# thing-plus-carrier.net
KiCad netlist of a schematic drawn in EAGLE
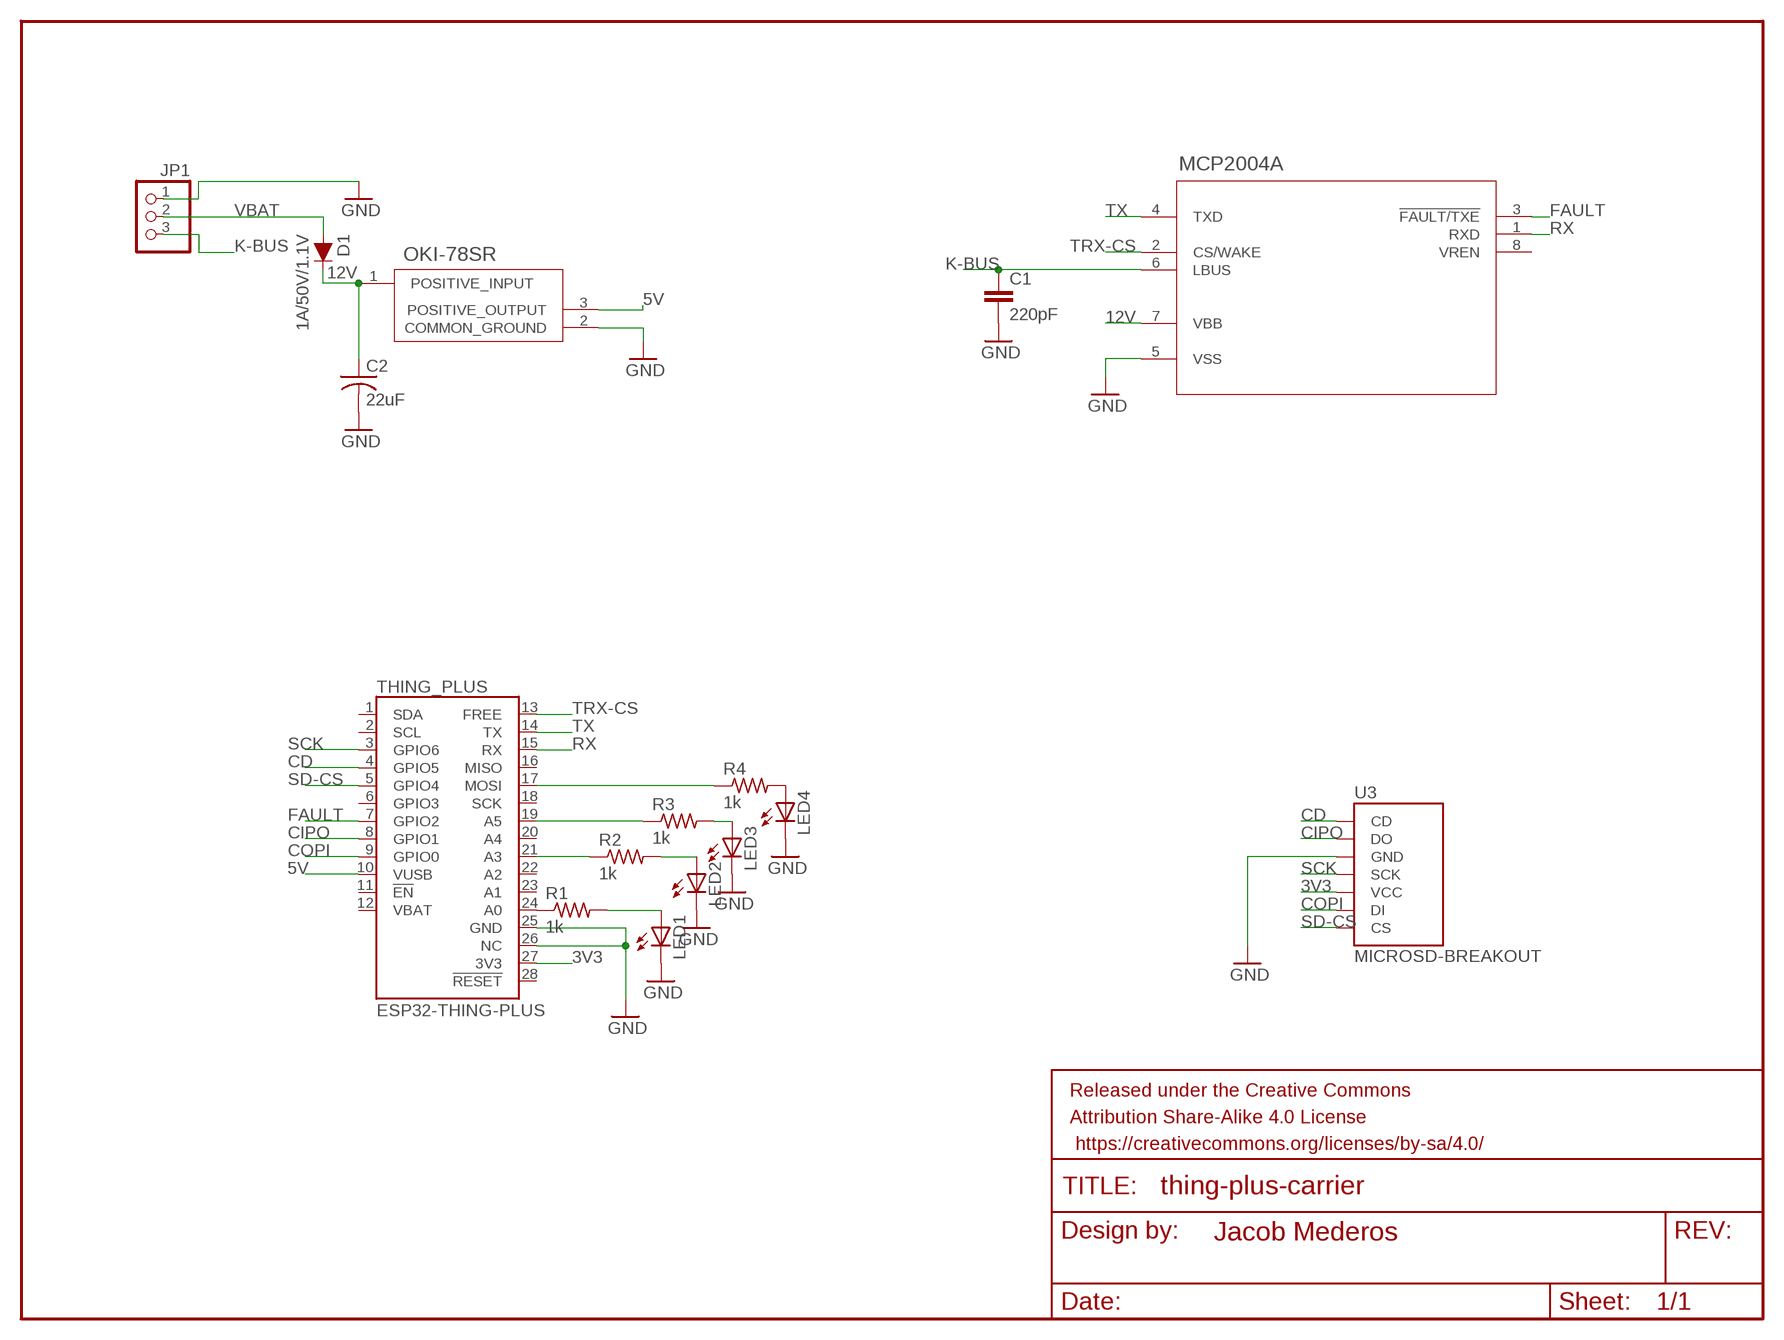
[diagram p0: schematic, sheet 1]

(export (version "E")
  (design (tool "Eeschema 10.0.6"))
  (components
    (comp (ref "C1")
      (value "220pF")
      (footprint "eagle-import:CAP-PTH-SMALL-KIT")
      (libsource (lib "eagle-import") (part "0.1UF-KIT-EZ-50V-20%"))
    )
    (comp (ref "C2")
      (value "22uF")
      (footprint "eagle-import:C1206K")
      (libsource (lib "eagle-import") (part "C-USC1206K"))
    )
    (comp (ref "D1")
      (value "1A/50V/1.1V")
      (footprint "eagle-import:DIODE-1N4001")
      (libsource (lib "eagle-import") (part "DIODE-PTH"))
    )
    (comp (ref "ESP32-THING-PLUS")
      (value "THING_PLUS")
      (footprint "eagle-import:THING_PLUS")
      (libsource (lib "eagle-import") (part "THING_PLUS"))
    )
    (comp (ref "FRAME1")
      (value "FRAME-LETTERNO_PACKAGE")
      (footprint "eagle-import:DUMMY")
      (fields (field (name "DESIGNER") "Jacob Mederos") (field (name "DESIGNER_1") "Jacob Mederos"))
      (libsource (lib "eagle-import") (part "FRAME-LETTERNO_PACKAGE"))
    )
    (comp (ref "JP1")
      (value "PINHD-1X3")
      (footprint "eagle-import:1X03")
      (libsource (lib "eagle-import") (part "PINHD-1X3"))
    )
    (comp (ref "LED1")
      (value "LEDCHIPLED_0805")
      (footprint "eagle-import:CHIPLED_0805")
      (libsource (lib "eagle-import") (part "LEDCHIPLED_0805"))
    )
    (comp (ref "LED2")
      (value "LEDCHIPLED_0805")
      (footprint "eagle-import:CHIPLED_0805")
      (libsource (lib "eagle-import") (part "LEDCHIPLED_0805"))
    )
    (comp (ref "LED3")
      (value "LEDCHIPLED_0805")
      (footprint "eagle-import:CHIPLED_0805")
      (libsource (lib "eagle-import") (part "LEDCHIPLED_0805"))
    )
    (comp (ref "LED4")
      (value "LEDCHIPLED_0805")
      (footprint "eagle-import:CHIPLED_0805")
      (libsource (lib "eagle-import") (part "LEDCHIPLED_0805"))
    )
    (comp (ref "MCP2004A")
      (value "MCP2004A-E/SNSOIC8_4P9X3P9MC_MCH-M")
      (footprint "eagle-import:SOIC8_4P9X3P9MC_MCH-M")
      (fields
        (field (name "MANUFACTURER_PART_NUMBER") "MCP2004A-E/SN")
        (field (name "COPYRIGHT") "Copyright (C) 2018 Accelerated Designs. All rights reserved")
      )
      (libsource (lib "eagle-import") (part "MCP2004A-E/SNSOIC8_4P9X3P9MC_MCH-M"))
    )
    (comp (ref "OKI-78SR")
      (value "OKI-78SR-5/1.5-W36H-C")
      (footprint "eagle-import:OKI-78SR-5_1.5-W36H-C_MUR")
      (fields (field (name "COPYRIGHT") "Copyright (C) 2018 Accelerated Designs. All rights reserved"))
      (libsource (lib "eagle-import") (part "OKI-78SR-5/1.5-W36H-C"))
    )
    (comp (ref "R1")
      (value "1k")
      (footprint "eagle-import:R0805")
      (libsource (lib "eagle-import") (part "R-US_R0805"))
    )
    (comp (ref "R2")
      (value "1k")
      (footprint "eagle-import:R0805")
      (libsource (lib "eagle-import") (part "R-US_R0805"))
    )
    (comp (ref "R3")
      (value "1k")
      (footprint "eagle-import:R0805")
      (libsource (lib "eagle-import") (part "R-US_R0805"))
    )
    (comp (ref "R4")
      (value "1k")
      (footprint "eagle-import:R0805")
      (libsource (lib "eagle-import") (part "R-US_R0805"))
    )
    (comp (ref "U3")
      (value "MICROSD-BREAKOUT")
      (footprint "eagle-import:MICROSD-BREAKOUT")
      (libsource (lib "eagle-import") (part "MICROSD-BREAKOUT"))
    )
  )
  (nets
    (net (code "1") (name "/3V3") (class "Default")
      (node (ref "ESP32-THING-PLUS") (pin "27") (pinfunction "3V3_27") (pintype "bidirectional"))
      (node (ref "U3") (pin "VCC") (pinfunction "VCC_VCC") (pintype "bidirectional"))
    )
    (net (code "2") (name "/5V") (class "Default")
      (node (ref "ESP32-THING-PLUS") (pin "10") (pinfunction "VUSB_10") (pintype "bidirectional"))
      (node (ref "OKI-78SR") (pin "3") (pinfunction "POSITIVE_OUTPUT_3") (pintype "passive"))
    )
    (net (code "3") (name "/12V") (class "Default")
      (node (ref "C2") (pin "1") (pinfunction "1_1") (pintype "passive"))
      (node (ref "D1") (pin "C") (pinfunction "C_C") (pintype "passive"))
      (node (ref "MCP2004A") (pin "7") (pinfunction "VBB_7") (pintype "power_in"))
      (node (ref "OKI-78SR") (pin "1") (pinfunction "POSITIVE_INPUT_1") (pintype "input"))
    )
    (net (code "4") (name "/CD") (class "Default")
      (node (ref "ESP32-THING-PLUS") (pin "4") (pinfunction "GPIO5_4") (pintype "bidirectional"))
      (node (ref "U3") (pin "CD") (pinfunction "CD_CD") (pintype "bidirectional"))
    )
    (net (code "5") (name "/CIPO") (class "Default")
      (node (ref "ESP32-THING-PLUS") (pin "8") (pinfunction "GPIO1_8") (pintype "bidirectional"))
      (node (ref "U3") (pin "DO") (pinfunction "DO_DO") (pintype "bidirectional"))
    )
    (net (code "6") (name "/COPI") (class "Default")
      (node (ref "ESP32-THING-PLUS") (pin "9") (pinfunction "GPIO0_9") (pintype "bidirectional"))
      (node (ref "U3") (pin "DI") (pinfunction "DI_DI") (pintype "bidirectional"))
    )
    (net (code "7") (name "/FAULT") (class "Default")
      (node (ref "ESP32-THING-PLUS") (pin "7") (pinfunction "GPIO2_7") (pintype "bidirectional"))
      (node (ref "MCP2004A") (pin "3") (pinfunction "~{FAULT/TXE}_3") (pintype "output"))
    )
    (net (code "8") (name "/K-BUS") (class "Default")
      (node (ref "C1") (pin "1") (pinfunction "1_1") (pintype "passive"))
      (node (ref "JP1") (pin "3") (pinfunction "3_3") (pintype "passive"))
      (node (ref "MCP2004A") (pin "6") (pinfunction "LBUS_6") (pintype "bidirectional"))
    )
    (net (code "9") (name "/RX") (class "Default")
      (node (ref "ESP32-THING-PLUS") (pin "15") (pinfunction "RX_15") (pintype "bidirectional"))
      (node (ref "MCP2004A") (pin "1") (pinfunction "RXD_1") (pintype "output"))
    )
    (net (code "10") (name "/SCK") (class "Default")
      (node (ref "ESP32-THING-PLUS") (pin "3") (pinfunction "GPIO6_3") (pintype "bidirectional"))
      (node (ref "U3") (pin "SCK") (pinfunction "SCK_SCK") (pintype "bidirectional"))
    )
    (net (code "11") (name "/SD-CS") (class "Default")
      (node (ref "ESP32-THING-PLUS") (pin "5") (pinfunction "GPIO4_5") (pintype "bidirectional"))
      (node (ref "U3") (pin "CS") (pinfunction "CS_CS") (pintype "bidirectional"))
    )
    (net (code "12") (name "/TRX-CS") (class "Default")
      (node (ref "ESP32-THING-PLUS") (pin "13") (pinfunction "FREE_13") (pintype "bidirectional"))
      (node (ref "MCP2004A") (pin "2") (pinfunction "CS/WAKE_2") (pintype "bidirectional"))
    )
    (net (code "13") (name "/TX") (class "Default")
      (node (ref "ESP32-THING-PLUS") (pin "14") (pinfunction "TX_14") (pintype "bidirectional"))
      (node (ref "MCP2004A") (pin "4") (pinfunction "TXD_4") (pintype "input"))
    )
    (net (code "14") (name "/VBAT") (class "Default")
      (node (ref "D1") (pin "A") (pinfunction "A_A") (pintype "passive"))
      (node (ref "JP1") (pin "2") (pinfunction "2_2") (pintype "passive"))
    )
    (net (code "15") (name "GND") (class "Default")
      (node (ref "C1") (pin "2") (pinfunction "2_2") (pintype "passive"))
      (node (ref "C2") (pin "2") (pinfunction "2_2") (pintype "passive"))
      (node (ref "ESP32-THING-PLUS") (pin "25") (pinfunction "GND_25") (pintype "bidirectional"))
      (node (ref "ESP32-THING-PLUS") (pin "26") (pinfunction "NC_26") (pintype "bidirectional"))
      (node (ref "JP1") (pin "1") (pinfunction "1_1") (pintype "passive"))
      (node (ref "LED1") (pin "C") (pinfunction "C_C") (pintype "passive"))
      (node (ref "LED2") (pin "C") (pinfunction "C_C") (pintype "passive"))
      (node (ref "LED3") (pin "C") (pinfunction "C_C") (pintype "passive"))
      (node (ref "LED4") (pin "C") (pinfunction "C_C") (pintype "passive"))
      (node (ref "MCP2004A") (pin "5") (pinfunction "VSS_5") (pintype "power_in"))
      (node (ref "OKI-78SR") (pin "2") (pinfunction "COMMON_GROUND_2") (pintype "passive"))
      (node (ref "U3") (pin "GND") (pinfunction "GND_GND") (pintype "power_in"))
    )
    (net (code "16") (name "Net-(ESP32-THING-PLUS-A0)") (class "Default")
      (node (ref "ESP32-THING-PLUS") (pin "24") (pinfunction "A0_24") (pintype "bidirectional"))
      (node (ref "R1") (pin "1") (pinfunction "1_1") (pintype "passive"))
    )
    (net (code "17") (name "Net-(ESP32-THING-PLUS-A3)") (class "Default")
      (node (ref "ESP32-THING-PLUS") (pin "21") (pinfunction "A3_21") (pintype "bidirectional"))
      (node (ref "R2") (pin "1") (pinfunction "1_1") (pintype "passive"))
    )
    (net (code "18") (name "Net-(ESP32-THING-PLUS-A5)") (class "Default")
      (node (ref "ESP32-THING-PLUS") (pin "19") (pinfunction "A5_19") (pintype "bidirectional"))
      (node (ref "R3") (pin "1") (pinfunction "1_1") (pintype "passive"))
    )
    (net (code "19") (name "Net-(ESP32-THING-PLUS-MOSI)") (class "Default")
      (node (ref "ESP32-THING-PLUS") (pin "17") (pinfunction "MOSI_17") (pintype "bidirectional"))
      (node (ref "R4") (pin "1") (pinfunction "1_1") (pintype "passive"))
    )
    (net (code "20") (name "Net-(LED1-PadA)") (class "Default")
      (node (ref "LED1") (pin "A") (pinfunction "A_A") (pintype "passive"))
      (node (ref "R1") (pin "2") (pinfunction "2_2") (pintype "passive"))
    )
    (net (code "21") (name "Net-(LED2-PadA)") (class "Default")
      (node (ref "LED2") (pin "A") (pinfunction "A_A") (pintype "passive"))
      (node (ref "R2") (pin "2") (pinfunction "2_2") (pintype "passive"))
    )
    (net (code "22") (name "Net-(LED3-PadA)") (class "Default")
      (node (ref "LED3") (pin "A") (pinfunction "A_A") (pintype "passive"))
      (node (ref "R3") (pin "2") (pinfunction "2_2") (pintype "passive"))
    )
    (net (code "23") (name "Net-(LED4-PadA)") (class "Default")
      (node (ref "LED4") (pin "A") (pinfunction "A_A") (pintype "passive"))
      (node (ref "R4") (pin "2") (pinfunction "2_2") (pintype "passive"))
    )
    (net (code "24") (name "unconnected-(ESP32-THING-PLUS-A1-Pad23)") (class "Default")
      (node (ref "ESP32-THING-PLUS") (pin "23") (pinfunction "A1_23") (pintype "bidirectional"))
    )
    (net (code "25") (name "unconnected-(ESP32-THING-PLUS-A2-Pad22)") (class "Default")
      (node (ref "ESP32-THING-PLUS") (pin "22") (pinfunction "A2_22") (pintype "bidirectional"))
    )
    (net (code "26") (name "unconnected-(ESP32-THING-PLUS-A4-Pad20)") (class "Default")
      (node (ref "ESP32-THING-PLUS") (pin "20") (pinfunction "A4_20") (pintype "bidirectional"))
    )
    (net (code "27") (name "unconnected-(ESP32-THING-PLUS-GPIO3-Pad6)") (class "Default")
      (node (ref "ESP32-THING-PLUS") (pin "6") (pinfunction "GPIO3_6") (pintype "bidirectional"))
    )
    (net (code "28") (name "unconnected-(ESP32-THING-PLUS-MISO-Pad16)") (class "Default")
      (node (ref "ESP32-THING-PLUS") (pin "16") (pinfunction "MISO_16") (pintype "bidirectional"))
    )
    (net (code "29") (name "unconnected-(ESP32-THING-PLUS-SCK-Pad18)") (class "Default")
      (node (ref "ESP32-THING-PLUS") (pin "18") (pinfunction "SCK_18") (pintype "bidirectional"))
    )
    (net (code "30") (name "unconnected-(ESP32-THING-PLUS-SCL-Pad2)") (class "Default")
      (node (ref "ESP32-THING-PLUS") (pin "2") (pinfunction "SCL_2") (pintype "bidirectional"))
    )
    (net (code "31") (name "unconnected-(ESP32-THING-PLUS-SDA-Pad1)") (class "Default")
      (node (ref "ESP32-THING-PLUS") (pin "1") (pinfunction "SDA_1") (pintype "bidirectional"))
    )
    (net (code "32") (name "unconnected-(ESP32-THING-PLUS-VBAT-Pad12)") (class "Default")
      (node (ref "ESP32-THING-PLUS") (pin "12") (pinfunction "VBAT_12") (pintype "bidirectional"))
    )
    (net (code "33") (name "unconnected-(ESP32-THING-PLUS-~{EN}-Pad11)") (class "Default")
      (node (ref "ESP32-THING-PLUS") (pin "11") (pinfunction "~{EN}_11") (pintype "bidirectional"))
    )
    (net (code "34") (name "unconnected-(ESP32-THING-PLUS-~{RESET}-Pad28)") (class "Default")
      (node (ref "ESP32-THING-PLUS") (pin "28") (pinfunction "~{RESET}_28") (pintype "bidirectional"))
    )
    (net (code "35") (name "unconnected-(MCP2004A-VREN-Pad8)") (class "Default")
      (node (ref "MCP2004A") (pin "8") (pinfunction "VREN_8") (pintype "output"))
    )
  )
)
